# enterCode.net
KiCad netlist of a schematic drawn in EAGLE
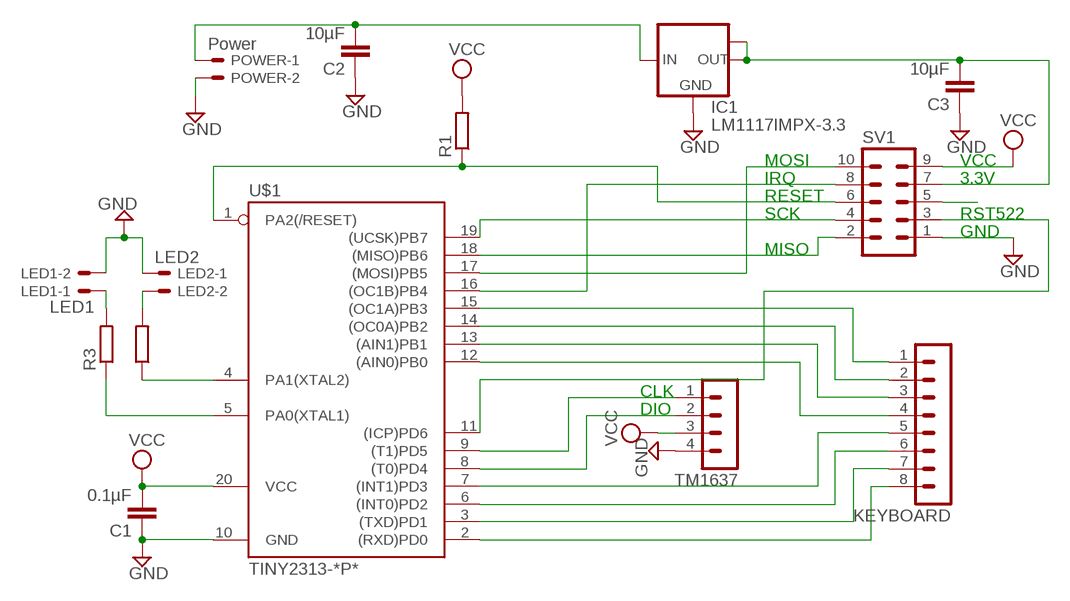
[diagram p0: schematic, sheet 1]

(export (version "E")
  (design (tool "Eeschema 10.0.6"))
  (components
    (comp (ref "C1")
      (value "0.1µF")
      (footprint "eagle-import:C2.5-4")
      (libsource (lib "eagle-import") (part "C2.5/4"))
    )
    (comp (ref "C2")
      (value "10µF")
      (footprint "eagle-import:C2.5-4")
      (libsource (lib "eagle-import") (part "C2.5/4"))
    )
    (comp (ref "C3")
      (value "10µF")
      (footprint "eagle-import:C2.5-4")
      (libsource (lib "eagle-import") (part "C2.5/4"))
    )
    (comp (ref "IC1")
      (value "LM1117IMPX-3.3")
      (footprint "eagle-import:SOT223")
      (libsource (lib "eagle-import") (part "LM1117IMPX-3.3"))
    )
    (comp (ref "KEYBOARD")
      (value "MA08-1")
      (footprint "eagle-import:MA08-1")
      (libsource (lib "eagle-import") (part "MA08-1"))
    )
    (comp (ref "LED1")
      (value "LED1")
      (footprint "eagle-import:22-23-2021")
      (fields (field (name "MF") "MOLEX") (field (name "MPN") "22-23-2021"))
      (libsource (lib "eagle-import") (part "22-23-2021"))
    )
    (comp (ref "LED2")
      (value "LED2")
      (footprint "eagle-import:22-23-2021")
      (fields (field (name "MF") "MOLEX") (field (name "MPN") "22-23-2021"))
      (libsource (lib "eagle-import") (part "22-23-2021"))
    )
    (comp (ref "POWER")
      (value "Power")
      (footprint "eagle-import:22-23-2021")
      (fields (field (name "MF") "MOLEX") (field (name "MPN") "22-23-2021"))
      (libsource (lib "eagle-import") (part "22-23-2021"))
    )
    (comp (ref "R1")
      (value "10k")
      (footprint "eagle-import:0207_10")
      (libsource (lib "eagle-import") (part "R-EU_0207/10"))
    )
    (comp (ref "R2")
      (value "470")
      (footprint "eagle-import:0207_10")
      (libsource (lib "eagle-import") (part "R-EU_0207/10"))
    )
    (comp (ref "R3")
      (value "470")
      (footprint "eagle-import:0207_10")
      (libsource (lib "eagle-import") (part "R-EU_0207/10"))
    )
    (comp (ref "SV1")
      (value "MA05-2")
      (footprint "eagle-import:MA05-2")
      (libsource (lib "eagle-import") (part "MA05-2"))
    )
    (comp (ref "TM1637")
      (value "MA04-1")
      (footprint "eagle-import:MA04-1")
      (libsource (lib "eagle-import") (part "MA04-1"))
    )
    (comp (ref "U$1")
      (value "TINY2313-*P*")
      (footprint "eagle-import:DIL20")
      (libsource (lib "eagle-import") (part "TINY2313-P"))
    )
  )
  (nets
    (net (code "1") (name "GND") (class "Default")
      (node (ref "C1") (pin "1") (pinfunction "1_1") (pintype "passive"))
      (node (ref "C2") (pin "1") (pinfunction "1_1") (pintype "passive"))
      (node (ref "C3") (pin "1") (pinfunction "1_1") (pintype "passive"))
      (node (ref "IC1") (pin "1") (pinfunction "GND_1") (pintype "input"))
      (node (ref "LED1") (pin "2") (pinfunction "S_2") (pintype "passive"))
      (node (ref "LED2") (pin "1") (pinfunction "S_1") (pintype "passive"))
      (node (ref "POWER") (pin "2") (pinfunction "S_2") (pintype "passive"))
      (node (ref "SV1") (pin "1") (pinfunction "1_1") (pintype "passive"))
      (node (ref "TM1637") (pin "4") (pinfunction "4_4") (pintype "passive"))
      (node (ref "U$1") (pin "10") (pinfunction "GND_10") (pintype "power_in"))
    )
    (net (code "2") (name "Net-(IC1-IN)") (class "Default")
      (node (ref "C2") (pin "2") (pinfunction "2_2") (pintype "passive"))
      (node (ref "IC1") (pin "3") (pinfunction "IN_3") (pintype "input"))
      (node (ref "POWER") (pin "1") (pinfunction "S_1") (pintype "passive"))
    )
    (net (code "3") (name "Net-(IC1-OUT)") (class "Default")
      (node (ref "C3") (pin "2") (pinfunction "2_2") (pintype "passive"))
      (node (ref "IC1") (pin "2") (pinfunction "OUT_2") (pintype "passive"))
      (node (ref "IC1") (pin "TAB") (pinfunction "OUT1_TAB") (pintype "passive"))
      (node (ref "SV1") (pin "7") (pinfunction "7_7") (pintype "passive"))
    )
    (net (code "4") (name "Net-(LED1A-S)") (class "Default")
      (node (ref "LED1") (pin "1") (pinfunction "S_1") (pintype "passive"))
      (node (ref "R3") (pin "2") (pinfunction "2_2") (pintype "passive"))
    )
    (net (code "5") (name "Net-(LED2B-S)") (class "Default")
      (node (ref "LED2") (pin "2") (pinfunction "S_2") (pintype "passive"))
      (node (ref "R2") (pin "2") (pinfunction "2_2") (pintype "passive"))
    )
    (net (code "6") (name "Net-(U$1-(AIN0)PB0)") (class "Default")
      (node (ref "KEYBOARD") (pin "4") (pinfunction "4_4") (pintype "passive"))
      (node (ref "U$1") (pin "12") (pinfunction "(AIN0)PB0_12") (pintype "bidirectional"))
    )
    (net (code "7") (name "Net-(U$1-(AIN1)PB1)") (class "Default")
      (node (ref "KEYBOARD") (pin "3") (pinfunction "3_3") (pintype "passive"))
      (node (ref "U$1") (pin "13") (pinfunction "(AIN1)PB1_13") (pintype "bidirectional"))
    )
    (net (code "8") (name "Net-(U$1-(ICP)PD6)") (class "Default")
      (node (ref "SV1") (pin "3") (pinfunction "3_3") (pintype "passive"))
      (node (ref "U$1") (pin "11") (pinfunction "(ICP)PD6_11") (pintype "bidirectional"))
    )
    (net (code "9") (name "Net-(U$1-(INT0)PD2)") (class "Default")
      (node (ref "KEYBOARD") (pin "6") (pinfunction "6_6") (pintype "passive"))
      (node (ref "U$1") (pin "6") (pinfunction "(INT0)PD2_6") (pintype "bidirectional"))
    )
    (net (code "10") (name "Net-(U$1-(INT1)PD3)") (class "Default")
      (node (ref "KEYBOARD") (pin "5") (pinfunction "5_5") (pintype "passive"))
      (node (ref "U$1") (pin "7") (pinfunction "(INT1)PD3_7") (pintype "bidirectional"))
    )
    (net (code "11") (name "Net-(U$1-(MISO)PB6)") (class "Default")
      (node (ref "SV1") (pin "2") (pinfunction "2_2") (pintype "passive"))
      (node (ref "U$1") (pin "18") (pinfunction "(MISO)PB6_18") (pintype "bidirectional"))
    )
    (net (code "12") (name "Net-(U$1-(MOSI)PB5)") (class "Default")
      (node (ref "SV1") (pin "10") (pinfunction "10_10") (pintype "passive"))
      (node (ref "U$1") (pin "17") (pinfunction "(MOSI)PB5_17") (pintype "bidirectional"))
    )
    (net (code "13") (name "Net-(U$1-(OC0A)PB2)") (class "Default")
      (node (ref "KEYBOARD") (pin "2") (pinfunction "2_2") (pintype "passive"))
      (node (ref "U$1") (pin "14") (pinfunction "(OC0A)PB2_14") (pintype "bidirectional"))
    )
    (net (code "14") (name "Net-(U$1-(OC1A)PB3)") (class "Default")
      (node (ref "KEYBOARD") (pin "1") (pinfunction "1_1") (pintype "passive"))
      (node (ref "U$1") (pin "15") (pinfunction "(OC1A)PB3_15") (pintype "bidirectional"))
    )
    (net (code "15") (name "Net-(U$1-(OC1B)PB4)") (class "Default")
      (node (ref "SV1") (pin "8") (pinfunction "8_8") (pintype "passive"))
      (node (ref "U$1") (pin "16") (pinfunction "(OC1B)PB4_16") (pintype "bidirectional"))
    )
    (net (code "16") (name "Net-(U$1-(RXD)PD0)") (class "Default")
      (node (ref "KEYBOARD") (pin "8") (pinfunction "8_8") (pintype "passive"))
      (node (ref "U$1") (pin "2") (pinfunction "(RXD)PD0_2") (pintype "bidirectional"))
    )
    (net (code "17") (name "Net-(U$1-(T0)PD4)") (class "Default")
      (node (ref "TM1637") (pin "2") (pinfunction "2_2") (pintype "passive"))
      (node (ref "U$1") (pin "8") (pinfunction "(T0)PD4_8") (pintype "bidirectional"))
    )
    (net (code "18") (name "Net-(U$1-(T1)PD5)") (class "Default")
      (node (ref "TM1637") (pin "1") (pinfunction "1_1") (pintype "passive"))
      (node (ref "U$1") (pin "9") (pinfunction "(T1)PD5_9") (pintype "bidirectional"))
    )
    (net (code "19") (name "Net-(U$1-(TXD)PD1)") (class "Default")
      (node (ref "KEYBOARD") (pin "7") (pinfunction "7_7") (pintype "passive"))
      (node (ref "U$1") (pin "3") (pinfunction "(TXD)PD1_3") (pintype "bidirectional"))
    )
    (net (code "20") (name "Net-(U$1-(UCSK)PB7)") (class "Default")
      (node (ref "SV1") (pin "4") (pinfunction "4_4") (pintype "passive"))
      (node (ref "U$1") (pin "19") (pinfunction "(UCSK)PB7_19") (pintype "bidirectional"))
    )
    (net (code "21") (name "Net-(U$1-PA0(XTAL1))") (class "Default")
      (node (ref "R3") (pin "1") (pinfunction "1_1") (pintype "passive"))
      (node (ref "U$1") (pin "5") (pinfunction "PA0(XTAL1)_5") (pintype "bidirectional"))
    )
    (net (code "22") (name "Net-(U$1-PA1(XTAL2))") (class "Default")
      (node (ref "R2") (pin "1") (pinfunction "1_1") (pintype "passive"))
      (node (ref "U$1") (pin "4") (pinfunction "PA1(XTAL2)_4") (pintype "bidirectional"))
    )
    (net (code "23") (name "Net-(U$1-PA2({slash}RESET))") (class "Default")
      (node (ref "R1") (pin "1") (pinfunction "1_1") (pintype "passive"))
      (node (ref "SV1") (pin "6") (pinfunction "6_6") (pintype "passive"))
      (node (ref "U$1") (pin "1") (pinfunction "PA2(/RESET)_1") (pintype "input"))
    )
    (net (code "24") (name "VCC") (class "Default")
      (node (ref "C1") (pin "2") (pinfunction "2_2") (pintype "passive"))
      (node (ref "R1") (pin "2") (pinfunction "2_2") (pintype "passive"))
      (node (ref "SV1") (pin "9") (pinfunction "9_9") (pintype "passive"))
      (node (ref "TM1637") (pin "3") (pinfunction "3_3") (pintype "passive"))
      (node (ref "U$1") (pin "20") (pinfunction "VCC_20") (pintype "power_in"))
    )
    (net (code "25") (name "unconnected-(SV1-Pad5)") (class "Default")
      (node (ref "SV1") (pin "5") (pinfunction "5_5") (pintype "passive"))
    )
  )
)
